# untitled.net
KiCad netlist of a schematic drawn in EAGLE
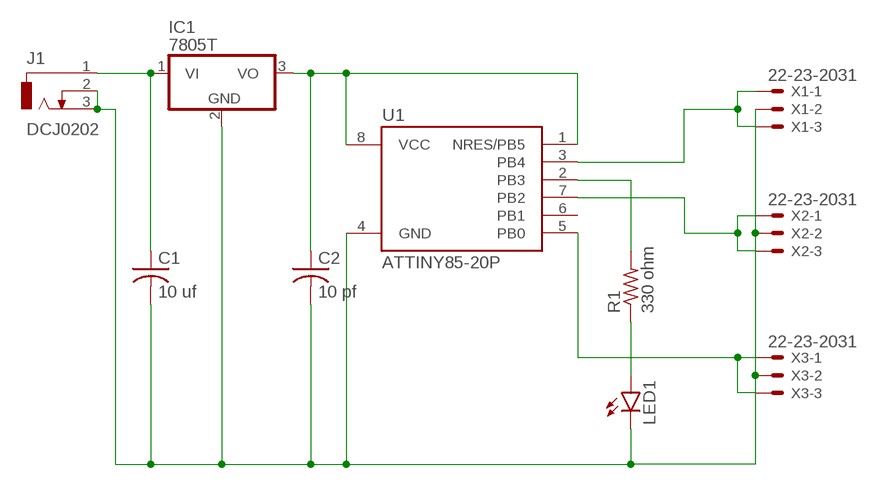
[diagram p0: schematic, sheet 1]

(export (version "E")
  (design (tool "Eeschema 10.0.6"))
  (components
    (comp (ref "C1")
      (value "10 uf")
      (footprint "eagle-import:C025-024X044")
      (libsource (lib "eagle-import") (part "C-US025-024X044"))
    )
    (comp (ref "C2")
      (value "10 pf")
      (footprint "eagle-import:C025-024X044")
      (libsource (lib "eagle-import") (part "C-US025-024X044"))
    )
    (comp (ref "IC1")
      (value "7805T")
      (footprint "eagle-import:TO220H")
      (libsource (lib "eagle-import") (part "78T05"))
    )
    (comp (ref "J1")
      (value "DCJ0202")
      (footprint "eagle-import:DCJ0202")
      (libsource (lib "eagle-import") (part "DCJ0202"))
    )
    (comp (ref "LED1")
      (value "LED3MM")
      (footprint "eagle-import:LED3MM")
      (libsource (lib "eagle-import") (part "LED3MM"))
    )
    (comp (ref "R1")
      (value "330 ohm")
      (footprint "eagle-import:0207_5V")
      (libsource (lib "eagle-import") (part "R-US_0207/5V"))
    )
    (comp (ref "U1")
      (value "ATTINY85-20P")
      (footprint "eagle-import:PDIP08_300MIL")
      (libsource (lib "eagle-import") (part "ATTINY85P-20"))
    )
    (comp (ref "X1")
      (value "22-23-2031")
      (footprint "eagle-import:22-23-2031")
      (fields (field (name "MF") "MOLEX"))
      (libsource (lib "eagle-import") (part "22-23-2031"))
    )
    (comp (ref "X2")
      (value "22-23-2031")
      (footprint "eagle-import:22-23-2031")
      (fields (field (name "MF") "MOLEX"))
      (libsource (lib "eagle-import") (part "22-23-2031"))
    )
    (comp (ref "X3")
      (value "22-23-2031")
      (footprint "eagle-import:22-23-2031")
      (fields (field (name "MF") "MOLEX"))
      (libsource (lib "eagle-import") (part "22-23-2031"))
    )
  )
  (nets
    (net (code "1") (name "Net-(IC1-GND)") (class "Default")
      (node (ref "C1") (pin "2") (pinfunction "2_2") (pintype "passive"))
      (node (ref "C2") (pin "2") (pinfunction "2_2") (pintype "passive"))
      (node (ref "IC1") (pin "2") (pinfunction "GND_2") (pintype "passive"))
      (node (ref "J1") (pin "2") (pinfunction "2_2") (pintype "passive"))
      (node (ref "J1") (pin "3") (pinfunction "3_3") (pintype "passive"))
      (node (ref "LED1") (pin "K") (pinfunction "C_K") (pintype "passive"))
      (node (ref "U1") (pin "4") (pinfunction "GND_4") (pintype "power_in"))
      (node (ref "X1") (pin "2") (pinfunction "S_2") (pintype "passive"))
      (node (ref "X2") (pin "2") (pinfunction "S_2") (pintype "passive"))
      (node (ref "X3") (pin "2") (pinfunction "S_2") (pintype "passive"))
    )
    (net (code "2") (name "Net-(IC1-VI)") (class "Default")
      (node (ref "C1") (pin "1") (pinfunction "1_1") (pintype "passive"))
      (node (ref "IC1") (pin "1") (pinfunction "VI_1") (pintype "input"))
      (node (ref "J1") (pin "1") (pinfunction "1_1") (pintype "passive"))
    )
    (net (code "3") (name "Net-(IC1-VO)") (class "Default")
      (node (ref "C2") (pin "1") (pinfunction "1_1") (pintype "passive"))
      (node (ref "IC1") (pin "3") (pinfunction "VO_3") (pintype "passive"))
      (node (ref "U1") (pin "1") (pinfunction "NRES/PB5_1") (pintype "bidirectional"))
      (node (ref "U1") (pin "8") (pinfunction "VCC_8") (pintype "power_in"))
    )
    (net (code "4") (name "Net-(LED1-PadA)") (class "Default")
      (node (ref "LED1") (pin "A") (pinfunction "A_A") (pintype "passive"))
      (node (ref "R1") (pin "1") (pinfunction "1_1") (pintype "passive"))
    )
    (net (code "5") (name "Net-(U1-PB0)") (class "Default")
      (node (ref "U1") (pin "5") (pinfunction "PB0_5") (pintype "bidirectional"))
      (node (ref "X3") (pin "1") (pinfunction "S_1") (pintype "passive"))
      (node (ref "X3") (pin "3") (pinfunction "S_3") (pintype "passive"))
    )
    (net (code "6") (name "Net-(U1-PB2)") (class "Default")
      (node (ref "U1") (pin "7") (pinfunction "PB2_7") (pintype "bidirectional"))
      (node (ref "X2") (pin "1") (pinfunction "S_1") (pintype "passive"))
      (node (ref "X2") (pin "3") (pinfunction "S_3") (pintype "passive"))
    )
    (net (code "7") (name "Net-(U1-PB3)") (class "Default")
      (node (ref "R1") (pin "2") (pinfunction "2_2") (pintype "passive"))
      (node (ref "U1") (pin "2") (pinfunction "PB3_2") (pintype "bidirectional"))
    )
    (net (code "8") (name "Net-(U1-PB4)") (class "Default")
      (node (ref "U1") (pin "3") (pinfunction "PB4_3") (pintype "bidirectional"))
      (node (ref "X1") (pin "1") (pinfunction "S_1") (pintype "passive"))
      (node (ref "X1") (pin "3") (pinfunction "S_3") (pintype "passive"))
    )
    (net (code "9") (name "unconnected-(U1-PB1-Pad6)") (class "Default")
      (node (ref "U1") (pin "6") (pinfunction "PB1_6") (pintype "bidirectional"))
    )
  )
)
